# D1_Mini_Pixel_Shield_V1_0.net
KiCad netlist of a schematic drawn in EAGLE
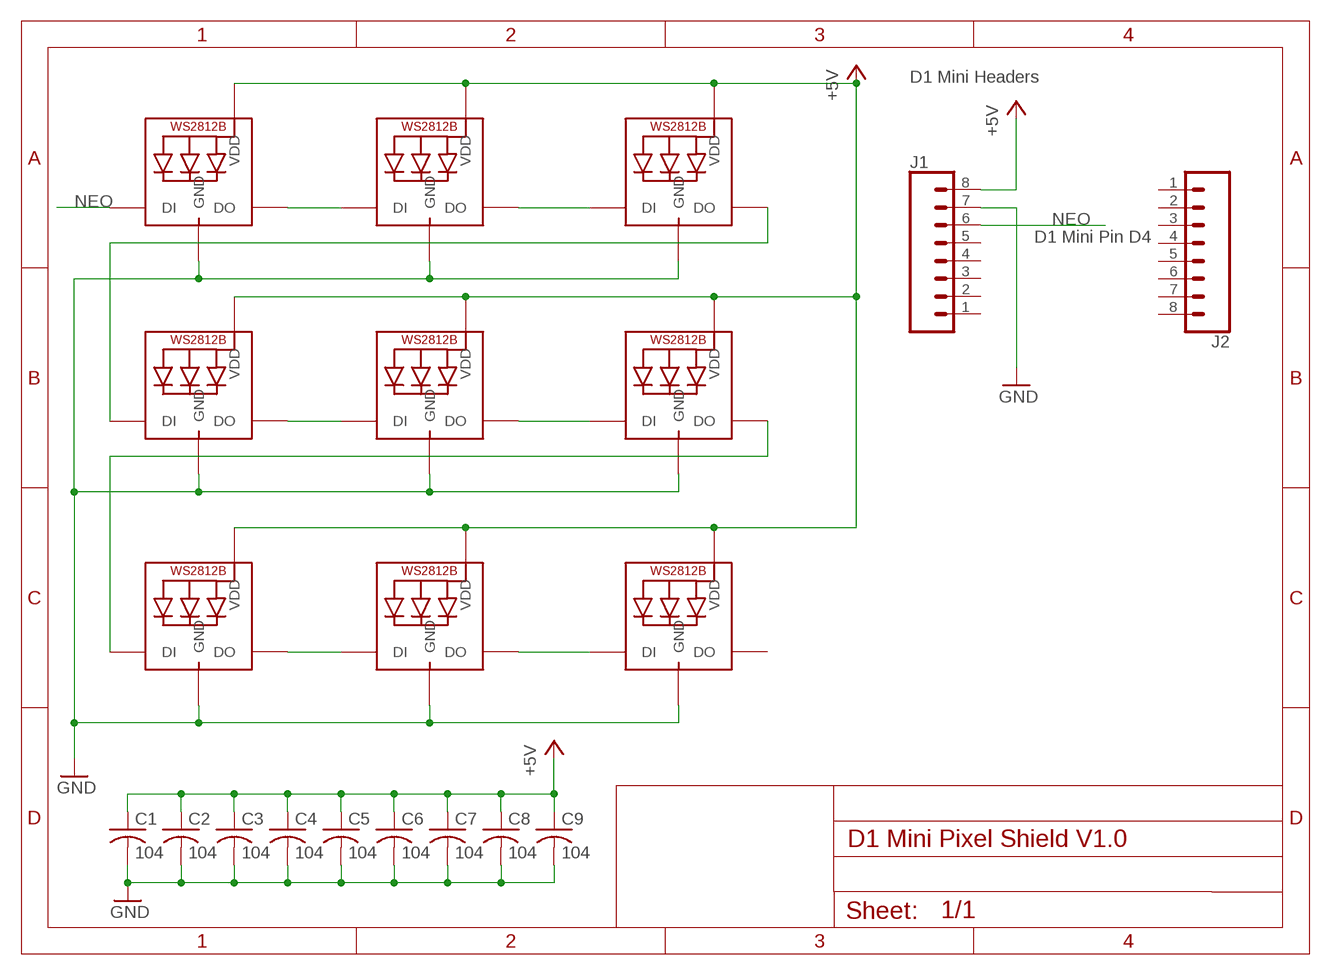
[diagram p0: schematic, sheet 1]

(export (version "E")
  (design (tool "Eeschema 10.0.6"))
  (components
    (comp (ref "C1")
      (value "104")
      (footprint "eagle-import:C0603")
      (libsource (lib "eagle-import") (part "C-USC0603"))
    )
    (comp (ref "C2")
      (value "104")
      (footprint "eagle-import:C0603")
      (libsource (lib "eagle-import") (part "C-USC0603"))
    )
    (comp (ref "C3")
      (value "104")
      (footprint "eagle-import:C0603")
      (libsource (lib "eagle-import") (part "C-USC0603"))
    )
    (comp (ref "C4")
      (value "104")
      (footprint "eagle-import:C0603")
      (libsource (lib "eagle-import") (part "C-USC0603"))
    )
    (comp (ref "C5")
      (value "104")
      (footprint "eagle-import:C0603")
      (libsource (lib "eagle-import") (part "C-USC0603"))
    )
    (comp (ref "C6")
      (value "104")
      (footprint "eagle-import:C0603")
      (libsource (lib "eagle-import") (part "C-USC0603"))
    )
    (comp (ref "C7")
      (value "104")
      (footprint "eagle-import:C0603")
      (libsource (lib "eagle-import") (part "C-USC0603"))
    )
    (comp (ref "C8")
      (value "104")
      (footprint "eagle-import:C0603")
      (libsource (lib "eagle-import") (part "C-USC0603"))
    )
    (comp (ref "C9")
      (value "104")
      (footprint "eagle-import:C0603")
      (libsource (lib "eagle-import") (part "C-USC0603"))
    )
    (comp (ref "J1")
      (value "CONN_08\"")
      (footprint "eagle-import:1X08")
      (libsource (lib "eagle-import") (part "CONN_08{dblquote}"))
    )
    (comp (ref "J2")
      (value "CONN_08\"")
      (footprint "eagle-import:1X08")
      (libsource (lib "eagle-import") (part "CONN_08{dblquote}"))
    )
    (comp (ref "LED1")
      (value "WS2812B_5050N")
      (footprint "eagle-import:WS2812B-NARROW")
      (libsource (lib "eagle-import") (part "WS2812B_5050N"))
    )
    (comp (ref "LED2")
      (value "WS2812B_5050N")
      (footprint "eagle-import:WS2812B-NARROW")
      (libsource (lib "eagle-import") (part "WS2812B_5050N"))
    )
    (comp (ref "LED3")
      (value "WS2812B_5050N")
      (footprint "eagle-import:WS2812B-NARROW")
      (libsource (lib "eagle-import") (part "WS2812B_5050N"))
    )
    (comp (ref "LED4")
      (value "WS2812B_5050N")
      (footprint "eagle-import:WS2812B-NARROW")
      (libsource (lib "eagle-import") (part "WS2812B_5050N"))
    )
    (comp (ref "LED5")
      (value "WS2812B_5050N")
      (footprint "eagle-import:WS2812B-NARROW")
      (libsource (lib "eagle-import") (part "WS2812B_5050N"))
    )
    (comp (ref "LED6")
      (value "WS2812B_5050N")
      (footprint "eagle-import:WS2812B-NARROW")
      (libsource (lib "eagle-import") (part "WS2812B_5050N"))
    )
    (comp (ref "LED7")
      (value "WS2812B_5050N")
      (footprint "eagle-import:WS2812B-NARROW")
      (libsource (lib "eagle-import") (part "WS2812B_5050N"))
    )
    (comp (ref "LED8")
      (value "WS2812B_5050N")
      (footprint "eagle-import:WS2812B-NARROW")
      (libsource (lib "eagle-import") (part "WS2812B_5050N"))
    )
    (comp (ref "LED9")
      (value "WS2812B_5050N")
      (footprint "eagle-import:WS2812B-NARROW")
      (libsource (lib "eagle-import") (part "WS2812B_5050N"))
    )
  )
  (nets
    (net (code "1") (name "+5V") (class "Default")
      (node (ref "C1") (pin "1") (pinfunction "1_1") (pintype "passive"))
      (node (ref "C2") (pin "1") (pinfunction "1_1") (pintype "passive"))
      (node (ref "C3") (pin "1") (pinfunction "1_1") (pintype "passive"))
      (node (ref "C4") (pin "1") (pinfunction "1_1") (pintype "passive"))
      (node (ref "C5") (pin "1") (pinfunction "1_1") (pintype "passive"))
      (node (ref "C6") (pin "1") (pinfunction "1_1") (pintype "passive"))
      (node (ref "C7") (pin "1") (pinfunction "1_1") (pintype "passive"))
      (node (ref "C8") (pin "1") (pinfunction "1_1") (pintype "passive"))
      (node (ref "C9") (pin "1") (pinfunction "1_1") (pintype "passive"))
      (node (ref "J1") (pin "8") (pinfunction "8_8") (pintype "passive"))
      (node (ref "LED1") (pin "1-VDD") (pinfunction "VDD_1-VDD") (pintype "power_in"))
      (node (ref "LED2") (pin "1-VDD") (pinfunction "VDD_1-VDD") (pintype "power_in"))
      (node (ref "LED3") (pin "1-VDD") (pinfunction "VDD_1-VDD") (pintype "power_in"))
      (node (ref "LED4") (pin "1-VDD") (pinfunction "VDD_1-VDD") (pintype "power_in"))
      (node (ref "LED5") (pin "1-VDD") (pinfunction "VDD_1-VDD") (pintype "power_in"))
      (node (ref "LED6") (pin "1-VDD") (pinfunction "VDD_1-VDD") (pintype "power_in"))
      (node (ref "LED7") (pin "1-VDD") (pinfunction "VDD_1-VDD") (pintype "power_in"))
      (node (ref "LED8") (pin "1-VDD") (pinfunction "VDD_1-VDD") (pintype "power_in"))
      (node (ref "LED9") (pin "1-VDD") (pinfunction "VDD_1-VDD") (pintype "power_in"))
    )
    (net (code "2") (name "/NEO") (class "Default")
      (node (ref "J1") (pin "6") (pinfunction "6_6") (pintype "passive"))
      (node (ref "LED1") (pin "4-DIN") (pinfunction "DI_4-DIN") (pintype "input"))
    )
    (net (code "3") (name "GND") (class "Default")
      (node (ref "C1") (pin "2") (pinfunction "2_2") (pintype "passive"))
      (node (ref "C2") (pin "2") (pinfunction "2_2") (pintype "passive"))
      (node (ref "C3") (pin "2") (pinfunction "2_2") (pintype "passive"))
      (node (ref "C4") (pin "2") (pinfunction "2_2") (pintype "passive"))
      (node (ref "C5") (pin "2") (pinfunction "2_2") (pintype "passive"))
      (node (ref "C6") (pin "2") (pinfunction "2_2") (pintype "passive"))
      (node (ref "C7") (pin "2") (pinfunction "2_2") (pintype "passive"))
      (node (ref "C8") (pin "2") (pinfunction "2_2") (pintype "passive"))
      (node (ref "C9") (pin "2") (pinfunction "2_2") (pintype "passive"))
      (node (ref "J1") (pin "7") (pinfunction "7_7") (pintype "passive"))
      (node (ref "LED1") (pin "3-GND") (pinfunction "GND_3-GND") (pintype "power_in"))
      (node (ref "LED2") (pin "3-GND") (pinfunction "GND_3-GND") (pintype "power_in"))
      (node (ref "LED3") (pin "3-GND") (pinfunction "GND_3-GND") (pintype "power_in"))
      (node (ref "LED4") (pin "3-GND") (pinfunction "GND_3-GND") (pintype "power_in"))
      (node (ref "LED5") (pin "3-GND") (pinfunction "GND_3-GND") (pintype "power_in"))
      (node (ref "LED6") (pin "3-GND") (pinfunction "GND_3-GND") (pintype "power_in"))
      (node (ref "LED7") (pin "3-GND") (pinfunction "GND_3-GND") (pintype "power_in"))
      (node (ref "LED8") (pin "3-GND") (pinfunction "GND_3-GND") (pintype "power_in"))
      (node (ref "LED9") (pin "3-GND") (pinfunction "GND_3-GND") (pintype "power_in"))
    )
    (net (code "4") (name "Net-(LED1-DO)") (class "Default")
      (node (ref "LED1") (pin "2-DOUT") (pinfunction "DO_2-DOUT") (pintype "output"))
      (node (ref "LED2") (pin "4-DIN") (pinfunction "DI_4-DIN") (pintype "input"))
    )
    (net (code "5") (name "Net-(LED2-DO)") (class "Default")
      (node (ref "LED2") (pin "2-DOUT") (pinfunction "DO_2-DOUT") (pintype "output"))
      (node (ref "LED3") (pin "4-DIN") (pinfunction "DI_4-DIN") (pintype "input"))
    )
    (net (code "6") (name "Net-(LED3-DO)") (class "Default")
      (node (ref "LED3") (pin "2-DOUT") (pinfunction "DO_2-DOUT") (pintype "output"))
      (node (ref "LED4") (pin "4-DIN") (pinfunction "DI_4-DIN") (pintype "input"))
    )
    (net (code "7") (name "Net-(LED4-DO)") (class "Default")
      (node (ref "LED4") (pin "2-DOUT") (pinfunction "DO_2-DOUT") (pintype "output"))
      (node (ref "LED5") (pin "4-DIN") (pinfunction "DI_4-DIN") (pintype "input"))
    )
    (net (code "8") (name "Net-(LED5-DO)") (class "Default")
      (node (ref "LED5") (pin "2-DOUT") (pinfunction "DO_2-DOUT") (pintype "output"))
      (node (ref "LED6") (pin "4-DIN") (pinfunction "DI_4-DIN") (pintype "input"))
    )
    (net (code "9") (name "Net-(LED6-DO)") (class "Default")
      (node (ref "LED6") (pin "2-DOUT") (pinfunction "DO_2-DOUT") (pintype "output"))
      (node (ref "LED7") (pin "4-DIN") (pinfunction "DI_4-DIN") (pintype "input"))
    )
    (net (code "10") (name "Net-(LED7-DO)") (class "Default")
      (node (ref "LED7") (pin "2-DOUT") (pinfunction "DO_2-DOUT") (pintype "output"))
      (node (ref "LED8") (pin "4-DIN") (pinfunction "DI_4-DIN") (pintype "input"))
    )
    (net (code "11") (name "Net-(LED8-DO)") (class "Default")
      (node (ref "LED8") (pin "2-DOUT") (pinfunction "DO_2-DOUT") (pintype "output"))
      (node (ref "LED9") (pin "4-DIN") (pinfunction "DI_4-DIN") (pintype "input"))
    )
    (net (code "12") (name "unconnected-(J1-Pad1)") (class "Default")
      (node (ref "J1") (pin "1") (pinfunction "1_1") (pintype "passive"))
    )
    (net (code "13") (name "unconnected-(J1-Pad2)") (class "Default")
      (node (ref "J1") (pin "2") (pinfunction "2_2") (pintype "passive"))
    )
    (net (code "14") (name "unconnected-(J1-Pad3)") (class "Default")
      (node (ref "J1") (pin "3") (pinfunction "3_3") (pintype "passive"))
    )
    (net (code "15") (name "unconnected-(J1-Pad4)") (class "Default")
      (node (ref "J1") (pin "4") (pinfunction "4_4") (pintype "passive"))
    )
    (net (code "16") (name "unconnected-(J1-Pad5)") (class "Default")
      (node (ref "J1") (pin "5") (pinfunction "5_5") (pintype "passive"))
    )
    (net (code "17") (name "unconnected-(J2-Pad1)") (class "Default")
      (node (ref "J2") (pin "1") (pinfunction "1_1") (pintype "passive"))
    )
    (net (code "18") (name "unconnected-(J2-Pad2)") (class "Default")
      (node (ref "J2") (pin "2") (pinfunction "2_2") (pintype "passive"))
    )
    (net (code "19") (name "unconnected-(J2-Pad3)") (class "Default")
      (node (ref "J2") (pin "3") (pinfunction "3_3") (pintype "passive"))
    )
    (net (code "20") (name "unconnected-(J2-Pad4)") (class "Default")
      (node (ref "J2") (pin "4") (pinfunction "4_4") (pintype "passive"))
    )
    (net (code "21") (name "unconnected-(J2-Pad5)") (class "Default")
      (node (ref "J2") (pin "5") (pinfunction "5_5") (pintype "passive"))
    )
    (net (code "22") (name "unconnected-(J2-Pad6)") (class "Default")
      (node (ref "J2") (pin "6") (pinfunction "6_6") (pintype "passive"))
    )
    (net (code "23") (name "unconnected-(J2-Pad7)") (class "Default")
      (node (ref "J2") (pin "7") (pinfunction "7_7") (pintype "passive"))
    )
    (net (code "24") (name "unconnected-(J2-Pad8)") (class "Default")
      (node (ref "J2") (pin "8") (pinfunction "8_8") (pintype "passive"))
    )
    (net (code "25") (name "unconnected-(LED9-DO-Pad2-DOUT)") (class "Default")
      (node (ref "LED9") (pin "2-DOUT") (pinfunction "DO_2-DOUT") (pintype "output"))
    )
  )
)
